# Encoder.net
KiCad netlist of a schematic drawn in EAGLE
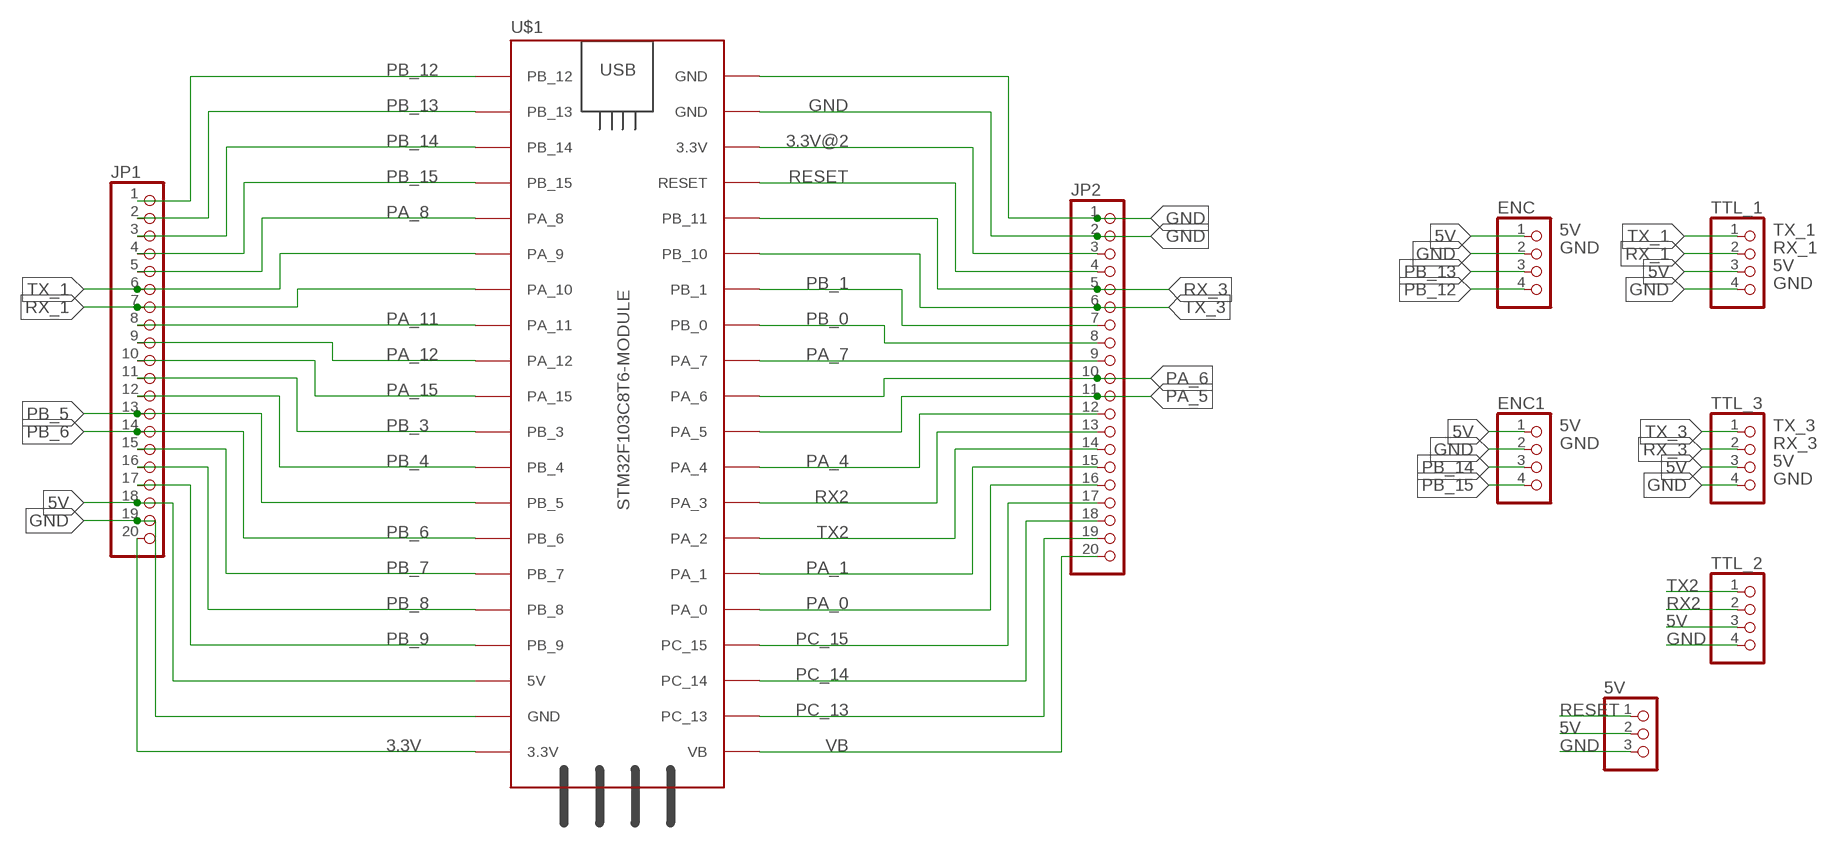
[diagram p0: schematic, sheet 1]

(export (version "E")
  (design (tool "Eeschema 10.0.6"))
  (components
    (comp (ref "5V")
      (value "PINHD-3_DATA")
      (footprint "eagle-import:1X03_DATA")
      (libsource (lib "eagle-import") (part "PINHD-3_DATA"))
    )
    (comp (ref "ENC")
      (value "PINHD-4_DATA")
      (footprint "eagle-import:1X04_DATA")
      (libsource (lib "eagle-import") (part "PINHD-4_DATA"))
    )
    (comp (ref "ENC1")
      (value "PINHD-4_DATA")
      (footprint "eagle-import:1X04_DATA")
      (libsource (lib "eagle-import") (part "PINHD-4_DATA"))
    )
    (comp (ref "JP1")
      (value "PINHD-1X20")
      (footprint "eagle-import:1X20")
      (libsource (lib "eagle-import") (part "PINHD-1X20"))
    )
    (comp (ref "JP2")
      (value "PINHD-1X20")
      (footprint "eagle-import:1X20")
      (libsource (lib "eagle-import") (part "PINHD-1X20"))
    )
    (comp (ref "TTL_1")
      (value "PINHD-4_DATA")
      (footprint "eagle-import:1X04_DATA")
      (libsource (lib "eagle-import") (part "PINHD-4_DATA"))
    )
    (comp (ref "TTL_2")
      (value "PINHD-4_DATA")
      (footprint "eagle-import:1X04_DATA")
      (libsource (lib "eagle-import") (part "PINHD-4_DATA"))
    )
    (comp (ref "TTL_3")
      (value "PINHD-4_DATA")
      (footprint "eagle-import:1X04_DATA")
      (libsource (lib "eagle-import") (part "PINHD-4_DATA"))
    )
    (comp (ref "U$1")
      (value "STM32F103C8T6-MODULE")
      (footprint "eagle-import:STM32F103C8T6-MODULE")
      (libsource (lib "eagle-import") (part "STM32F103C8T6-MODULE"))
    )
  )
  (nets
    (net (code "1") (name "/3.3V") (class "Default")
      (node (ref "JP1") (pin "20") (pinfunction "20_20") (pintype "passive"))
      (node (ref "U$1") (pin "3.3V_1") (pinfunction "3.3V_3.3V_1") (pintype "bidirectional"))
    )
    (net (code "2") (name "/3.3V@2") (class "Default")
      (node (ref "JP2") (pin "3") (pinfunction "3_3") (pintype "passive"))
      (node (ref "U$1") (pin "3.3V_2") (pinfunction "3.3V_3.3V_2") (pintype "bidirectional"))
    )
    (net (code "3") (name "/PA_0") (class "Default")
      (node (ref "JP2") (pin "16") (pinfunction "16_16") (pintype "passive"))
      (node (ref "U$1") (pin "PA_0") (pinfunction "PA_0_PA_0") (pintype "bidirectional"))
    )
    (net (code "4") (name "/PA_1") (class "Default")
      (node (ref "JP2") (pin "15") (pinfunction "15_15") (pintype "passive"))
      (node (ref "U$1") (pin "PA_1") (pinfunction "PA_1_PA_1") (pintype "bidirectional"))
    )
    (net (code "5") (name "/PA_4") (class "Default")
      (node (ref "JP2") (pin "12") (pinfunction "12_12") (pintype "passive"))
      (node (ref "U$1") (pin "PA_4") (pinfunction "PA_4_PA_4") (pintype "bidirectional"))
    )
    (net (code "6") (name "/PA_7") (class "Default")
      (node (ref "JP2") (pin "9") (pinfunction "9_9") (pintype "passive"))
      (node (ref "U$1") (pin "PA_7") (pinfunction "PA_7_PA_7") (pintype "bidirectional"))
    )
    (net (code "7") (name "/PA_8") (class "Default")
      (node (ref "JP1") (pin "5") (pinfunction "5_5") (pintype "passive"))
      (node (ref "U$1") (pin "PA_8") (pinfunction "PA_8_PA_8") (pintype "bidirectional"))
    )
    (net (code "8") (name "/PA_11") (class "Default")
      (node (ref "JP1") (pin "8") (pinfunction "8_8") (pintype "passive"))
      (node (ref "U$1") (pin "PA_11") (pinfunction "PA_11_PA_11") (pintype "bidirectional"))
    )
    (net (code "9") (name "/PA_12") (class "Default")
      (node (ref "JP1") (pin "9") (pinfunction "9_9") (pintype "passive"))
      (node (ref "U$1") (pin "PA_12") (pinfunction "PA_12_PA_12") (pintype "bidirectional"))
    )
    (net (code "10") (name "/PA_15") (class "Default")
      (node (ref "JP1") (pin "10") (pinfunction "10_10") (pintype "passive"))
      (node (ref "U$1") (pin "PA_15") (pinfunction "PA_15_PA_15") (pintype "bidirectional"))
    )
    (net (code "11") (name "/PB_0") (class "Default")
      (node (ref "JP2") (pin "8") (pinfunction "8_8") (pintype "passive"))
      (node (ref "U$1") (pin "PB_0") (pinfunction "PB_0_PB_0") (pintype "bidirectional"))
    )
    (net (code "12") (name "/PB_1") (class "Default")
      (node (ref "JP2") (pin "7") (pinfunction "7_7") (pintype "passive"))
      (node (ref "U$1") (pin "PB_1") (pinfunction "PB_1_PB_1") (pintype "bidirectional"))
    )
    (net (code "13") (name "/PB_3") (class "Default")
      (node (ref "JP1") (pin "11") (pinfunction "11_11") (pintype "passive"))
      (node (ref "U$1") (pin "PB_3") (pinfunction "PB_3_PB_3") (pintype "bidirectional"))
    )
    (net (code "14") (name "/PB_4") (class "Default")
      (node (ref "JP1") (pin "12") (pinfunction "12_12") (pintype "passive"))
      (node (ref "U$1") (pin "PB_4") (pinfunction "PB_4_PB_4") (pintype "bidirectional"))
    )
    (net (code "15") (name "/PB_7") (class "Default")
      (node (ref "JP1") (pin "15") (pinfunction "15_15") (pintype "passive"))
      (node (ref "U$1") (pin "PB_7") (pinfunction "PB_7_PB_7") (pintype "bidirectional"))
    )
    (net (code "16") (name "/PB_8") (class "Default")
      (node (ref "JP1") (pin "16") (pinfunction "16_16") (pintype "passive"))
      (node (ref "U$1") (pin "PB_8") (pinfunction "PB_8_PB_8") (pintype "bidirectional"))
    )
    (net (code "17") (name "/PB_9") (class "Default")
      (node (ref "JP1") (pin "17") (pinfunction "17_17") (pintype "passive"))
      (node (ref "U$1") (pin "PB_9") (pinfunction "PB_9_PB_9") (pintype "bidirectional"))
    )
    (net (code "18") (name "/PC_13") (class "Default")
      (node (ref "JP2") (pin "19") (pinfunction "19_19") (pintype "passive"))
      (node (ref "U$1") (pin "PC_13") (pinfunction "PC_13_PC_13") (pintype "bidirectional"))
    )
    (net (code "19") (name "/PC_14") (class "Default")
      (node (ref "JP2") (pin "18") (pinfunction "18_18") (pintype "passive"))
      (node (ref "U$1") (pin "PC_14") (pinfunction "PC_14_PC_14") (pintype "bidirectional"))
    )
    (net (code "20") (name "/PC_15") (class "Default")
      (node (ref "JP2") (pin "17") (pinfunction "17_17") (pintype "passive"))
      (node (ref "U$1") (pin "PC_15") (pinfunction "PC_15_PC_15") (pintype "bidirectional"))
    )
    (net (code "21") (name "/RESET") (class "Default")
      (node (ref "5V") (pin "1") (pinfunction "1_1") (pintype "passive"))
      (node (ref "JP2") (pin "4") (pinfunction "4_4") (pintype "passive"))
      (node (ref "U$1") (pin "RESET") (pinfunction "RESET_RESET") (pintype "bidirectional"))
    )
    (net (code "22") (name "/RX2") (class "Default")
      (node (ref "JP2") (pin "13") (pinfunction "13_13") (pintype "passive"))
      (node (ref "TTL_2") (pin "2") (pinfunction "2_2") (pintype "passive"))
      (node (ref "U$1") (pin "PA_3") (pinfunction "PA_3_PA_3") (pintype "bidirectional"))
    )
    (net (code "23") (name "/TX2") (class "Default")
      (node (ref "JP2") (pin "14") (pinfunction "14_14") (pintype "passive"))
      (node (ref "TTL_2") (pin "1") (pinfunction "1_1") (pintype "passive"))
      (node (ref "U$1") (pin "PA_2") (pinfunction "PA_2_PA_2") (pintype "bidirectional"))
    )
    (net (code "24") (name "/VB") (class "Default")
      (node (ref "JP2") (pin "20") (pinfunction "20_20") (pintype "passive"))
      (node (ref "U$1") (pin "VB") (pinfunction "VB_VB") (pintype "bidirectional"))
    )
    (net (code "25") (name "5V") (class "Default")
      (node (ref "5V") (pin "2") (pinfunction "2_2") (pintype "passive"))
      (node (ref "ENC") (pin "1") (pinfunction "1_1") (pintype "passive"))
      (node (ref "ENC1") (pin "1") (pinfunction "1_1") (pintype "passive"))
      (node (ref "JP1") (pin "18") (pinfunction "18_18") (pintype "passive"))
      (node (ref "TTL_1") (pin "3") (pinfunction "3_3") (pintype "passive"))
      (node (ref "TTL_2") (pin "3") (pinfunction "3_3") (pintype "passive"))
      (node (ref "TTL_3") (pin "3") (pinfunction "3_3") (pintype "passive"))
      (node (ref "U$1") (pin "5V") (pinfunction "5V_5V") (pintype "bidirectional"))
    )
    (net (code "26") (name "GND") (class "Default")
      (node (ref "5V") (pin "3") (pinfunction "3_3") (pintype "passive"))
      (node (ref "ENC") (pin "2") (pinfunction "2_2") (pintype "passive"))
      (node (ref "ENC1") (pin "2") (pinfunction "2_2") (pintype "passive"))
      (node (ref "JP1") (pin "19") (pinfunction "19_19") (pintype "passive"))
      (node (ref "JP2") (pin "1") (pinfunction "1_1") (pintype "passive"))
      (node (ref "JP2") (pin "2") (pinfunction "2_2") (pintype "passive"))
      (node (ref "TTL_1") (pin "4") (pinfunction "4_4") (pintype "passive"))
      (node (ref "TTL_2") (pin "4") (pinfunction "4_4") (pintype "passive"))
      (node (ref "TTL_3") (pin "4") (pinfunction "4_4") (pintype "passive"))
      (node (ref "U$1") (pin "GND_1") (pinfunction "GND_GND_1") (pintype "bidirectional"))
      (node (ref "U$1") (pin "GND_2") (pinfunction "GND_GND_2") (pintype "bidirectional"))
      (node (ref "U$1") (pin "GND_3") (pinfunction "GND_GND_3") (pintype "power_in"))
    )
    (net (code "27") (name "PA_5") (class "Default")
      (node (ref "JP2") (pin "11") (pinfunction "11_11") (pintype "passive"))
      (node (ref "U$1") (pin "PA_5") (pinfunction "PA_5_PA_5") (pintype "bidirectional"))
    )
    (net (code "28") (name "PA_6") (class "Default")
      (node (ref "JP2") (pin "10") (pinfunction "10_10") (pintype "passive"))
      (node (ref "U$1") (pin "PA_6") (pinfunction "PA_6_PA_6") (pintype "bidirectional"))
    )
    (net (code "29") (name "PB_5") (class "Default")
      (node (ref "JP1") (pin "13") (pinfunction "13_13") (pintype "passive"))
      (node (ref "U$1") (pin "PB_5") (pinfunction "PB_5_PB_5") (pintype "bidirectional"))
    )
    (net (code "30") (name "PB_6") (class "Default")
      (node (ref "JP1") (pin "14") (pinfunction "14_14") (pintype "passive"))
      (node (ref "U$1") (pin "PB_6") (pinfunction "PB_6_PB_6") (pintype "bidirectional"))
    )
    (net (code "31") (name "PB_12") (class "Default")
      (node (ref "ENC") (pin "4") (pinfunction "4_4") (pintype "passive"))
      (node (ref "JP1") (pin "1") (pinfunction "1_1") (pintype "passive"))
      (node (ref "U$1") (pin "PB_12") (pinfunction "PB_12_PB_12") (pintype "bidirectional"))
    )
    (net (code "32") (name "PB_13") (class "Default")
      (node (ref "ENC") (pin "3") (pinfunction "3_3") (pintype "passive"))
      (node (ref "JP1") (pin "2") (pinfunction "2_2") (pintype "passive"))
      (node (ref "U$1") (pin "PB_13") (pinfunction "PB_13_PB_13") (pintype "bidirectional"))
    )
    (net (code "33") (name "PB_14") (class "Default")
      (node (ref "ENC1") (pin "3") (pinfunction "3_3") (pintype "passive"))
      (node (ref "JP1") (pin "3") (pinfunction "3_3") (pintype "passive"))
      (node (ref "U$1") (pin "PB_14") (pinfunction "PB_14_PB_14") (pintype "bidirectional"))
    )
    (net (code "34") (name "PB_15") (class "Default")
      (node (ref "ENC1") (pin "4") (pinfunction "4_4") (pintype "passive"))
      (node (ref "JP1") (pin "4") (pinfunction "4_4") (pintype "passive"))
      (node (ref "U$1") (pin "PB_15") (pinfunction "PB_15_PB_15") (pintype "bidirectional"))
    )
    (net (code "35") (name "RX_1") (class "Default")
      (node (ref "JP1") (pin "7") (pinfunction "7_7") (pintype "passive"))
      (node (ref "TTL_1") (pin "2") (pinfunction "2_2") (pintype "passive"))
      (node (ref "U$1") (pin "PA_10") (pinfunction "PA_10_PA_10") (pintype "bidirectional"))
    )
    (net (code "36") (name "RX_3") (class "Default")
      (node (ref "JP2") (pin "5") (pinfunction "5_5") (pintype "passive"))
      (node (ref "TTL_3") (pin "2") (pinfunction "2_2") (pintype "passive"))
      (node (ref "U$1") (pin "PB_11") (pinfunction "PB_11_PB_11") (pintype "bidirectional"))
    )
    (net (code "37") (name "TX_1") (class "Default")
      (node (ref "JP1") (pin "6") (pinfunction "6_6") (pintype "passive"))
      (node (ref "TTL_1") (pin "1") (pinfunction "1_1") (pintype "passive"))
      (node (ref "U$1") (pin "PA_9") (pinfunction "PA_9_PA_9") (pintype "bidirectional"))
    )
    (net (code "38") (name "TX_3") (class "Default")
      (node (ref "JP2") (pin "6") (pinfunction "6_6") (pintype "passive"))
      (node (ref "TTL_3") (pin "1") (pinfunction "1_1") (pintype "passive"))
      (node (ref "U$1") (pin "PB_10") (pinfunction "PB_10_PB_10") (pintype "bidirectional"))
    )
  )
)
